# K3NG_Rotator_Interface_V2.net
KiCad netlist of a schematic drawn in EAGLE
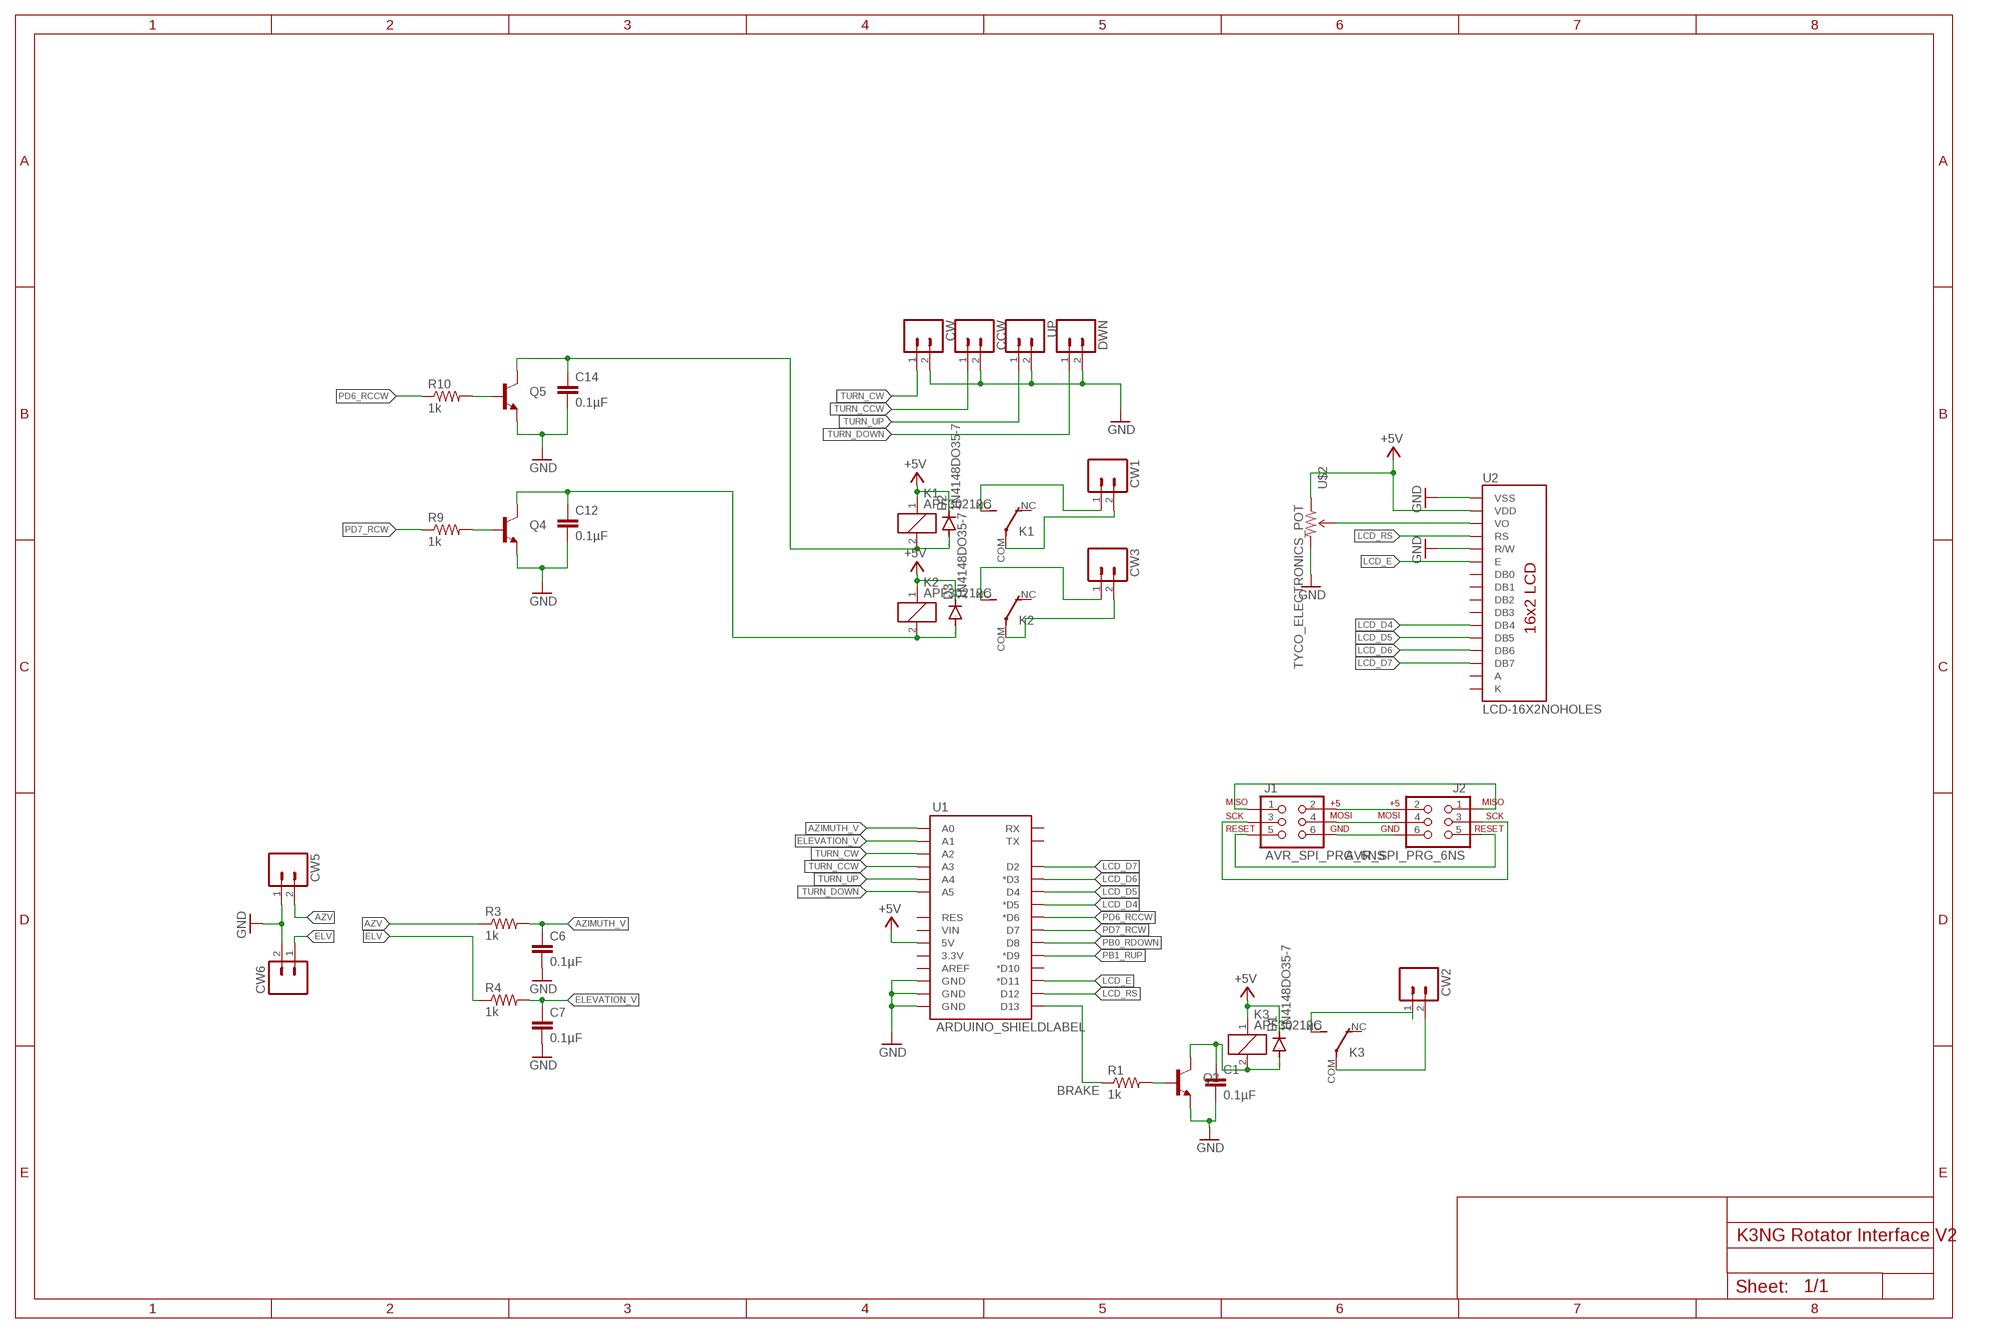
[diagram p0: schematic, sheet 1]

(export (version "E")
  (design (tool "Eeschema 10.0.6"))
  (components
    (comp (ref "C1")
      (value "0.1µF")
      (footprint "eagle-import:0603-CAP")
      (libsource (lib "eagle-import") (part "CAP0603-CAP"))
    )
    (comp (ref "C6")
      (value "0.1µF")
      (footprint "eagle-import:0603-CAP")
      (libsource (lib "eagle-import") (part "CAP0603-CAP"))
    )
    (comp (ref "C7")
      (value "0.1µF")
      (footprint "eagle-import:0603-CAP")
      (libsource (lib "eagle-import") (part "CAP0603-CAP"))
    )
    (comp (ref "C12")
      (value "0.1µF")
      (footprint "eagle-import:0603-CAP")
      (libsource (lib "eagle-import") (part "CAP0603-CAP"))
    )
    (comp (ref "C14")
      (value "0.1µF")
      (footprint "eagle-import:0603-CAP")
      (libsource (lib "eagle-import") (part "CAP0603-CAP"))
    )
    (comp (ref "CCW")
      (value "M02PTH")
      (footprint "eagle-import:1X02")
      (libsource (lib "eagle-import") (part "M02PTH"))
    )
    (comp (ref "CW")
      (value "M02PTH")
      (footprint "eagle-import:1X02")
      (libsource (lib "eagle-import") (part "M02PTH"))
    )
    (comp (ref "CW1")
      (value "M02PTH")
      (footprint "eagle-import:1X02")
      (libsource (lib "eagle-import") (part "M02PTH"))
    )
    (comp (ref "CW2")
      (value "M02PTH")
      (footprint "eagle-import:1X02")
      (libsource (lib "eagle-import") (part "M02PTH"))
    )
    (comp (ref "CW3")
      (value "M02PTH")
      (footprint "eagle-import:1X02")
      (libsource (lib "eagle-import") (part "M02PTH"))
    )
    (comp (ref "CW5")
      (value "M02PTH")
      (footprint "eagle-import:1X02")
      (libsource (lib "eagle-import") (part "M02PTH"))
    )
    (comp (ref "CW6")
      (value "M02PTH")
      (footprint "eagle-import:1X02")
      (libsource (lib "eagle-import") (part "M02PTH"))
    )
    (comp (ref "D1")
      (value "1N4148DO35-7")
      (footprint "eagle-import:DO35-7")
      (libsource (lib "eagle-import") (part "1N4148DO35-7"))
    )
    (comp (ref "D2")
      (value "1N4148DO35-7")
      (footprint "eagle-import:DO35-7")
      (libsource (lib "eagle-import") (part "1N4148DO35-7"))
    )
    (comp (ref "D3")
      (value "1N4148DO35-7")
      (footprint "eagle-import:DO35-7")
      (libsource (lib "eagle-import") (part "1N4148DO35-7"))
    )
    (comp (ref "DWN")
      (value "M02PTH")
      (footprint "eagle-import:1X02")
      (libsource (lib "eagle-import") (part "M02PTH"))
    )
    (comp (ref "J1")
      (value "AVR_SPI_PRG_6NS")
      (footprint "eagle-import:2X3-NS")
      (libsource (lib "eagle-import") (part "AVR_SPI_PRG_6NS"))
    )
    (comp (ref "J2")
      (value "AVR_SPI_PRG_6NS")
      (footprint "eagle-import:2X3-NS")
      (libsource (lib "eagle-import") (part "AVR_SPI_PRG_6NS"))
    )
    (comp (ref "K1")
      (value "APF30212C")
      (footprint "eagle-import:APF30212C")
      (libsource (lib "eagle-import") (part "APF30212C"))
    )
    (comp (ref "K2")
      (value "APF30212C")
      (footprint "eagle-import:APF30212C")
      (libsource (lib "eagle-import") (part "APF30212C"))
    )
    (comp (ref "K3")
      (value "APF30212C")
      (footprint "eagle-import:APF30212C")
      (libsource (lib "eagle-import") (part "APF30212C"))
    )
    (comp (ref "Q2")
      (value "TRANSISTOR_NPNSOT23")
      (footprint "eagle-import:SOT23")
      (libsource (lib "eagle-import") (part "TRANSISTOR_NPNSOT23"))
    )
    (comp (ref "Q4")
      (value "TRANSISTOR_NPNSOT23")
      (footprint "eagle-import:SOT23")
      (libsource (lib "eagle-import") (part "TRANSISTOR_NPNSOT23"))
    )
    (comp (ref "Q5")
      (value "TRANSISTOR_NPNSOT23")
      (footprint "eagle-import:SOT23")
      (libsource (lib "eagle-import") (part "TRANSISTOR_NPNSOT23"))
    )
    (comp (ref "R1")
      (value "1k")
      (footprint "eagle-import:0805")
      (libsource (lib "eagle-import") (part "RESISTOR0805-RES"))
    )
    (comp (ref "R3")
      (value "1k")
      (footprint "eagle-import:0805")
      (libsource (lib "eagle-import") (part "RESISTOR0805-RES"))
    )
    (comp (ref "R4")
      (value "1k")
      (footprint "eagle-import:0805")
      (libsource (lib "eagle-import") (part "RESISTOR0805-RES"))
    )
    (comp (ref "R9")
      (value "1k")
      (footprint "eagle-import:0805")
      (libsource (lib "eagle-import") (part "RESISTOR0805-RES"))
    )
    (comp (ref "R10")
      (value "1k")
      (footprint "eagle-import:0805")
      (libsource (lib "eagle-import") (part "RESISTOR0805-RES"))
    )
    (comp (ref "U$2")
      (value "TYCO_ELECTRONICS_POT")
      (footprint "eagle-import:TYCO_ELECTRONICS_POT")
      (libsource (lib "eagle-import") (part "TYCO_ELECTRONICS_POT"))
    )
    (comp (ref "U1")
      (value "ARDUINO_SHIELDLABEL")
      (footprint "eagle-import:DUEMILANOVE_SHIELD")
      (libsource (lib "eagle-import") (part "ARDUINO_SHIELDLABEL"))
    )
    (comp (ref "U2")
      (value "LCD-16X2NOHOLES")
      (footprint "eagle-import:LCD-16X2_NOHOLES")
      (libsource (lib "eagle-import") (part "LCD-16X2NOHOLES"))
    )
    (comp (ref "UP")
      (value "M02PTH")
      (footprint "eagle-import:1X02")
      (libsource (lib "eagle-import") (part "M02PTH"))
    )
  )
  (nets
    (net (code "1") (name "+5V") (class "Default")
      (node (ref "D1") (pin "C") (pinfunction "C_C") (pintype "passive"))
      (node (ref "D2") (pin "C") (pinfunction "C_C") (pintype "passive"))
      (node (ref "D3") (pin "C") (pinfunction "C_C") (pintype "passive"))
      (node (ref "K1") (pin "1") (pinfunction "1_1") (pintype "passive"))
      (node (ref "K2") (pin "1") (pinfunction "1_1") (pintype "passive"))
      (node (ref "K3") (pin "1") (pinfunction "1_1") (pintype "passive"))
      (node (ref "U$2") (pin "P$1") (pinfunction "CCW_P$1") (pintype "passive"))
      (node (ref "U1") (pin "5V") (pinfunction "5V_5V") (pintype "bidirectional"))
      (node (ref "U2") (pin "2") (pinfunction "VDD_2") (pintype "power_in"))
    )
    (net (code "2") (name "/A") (class "Default")
      (node (ref "U2") (pin "15") (pinfunction "A_15") (pintype "power_in"))
    )
    (net (code "3") (name "/BRAKE") (class "Default")
      (node (ref "R1") (pin "1") (pinfunction "1_1") (pintype "passive"))
      (node (ref "U1") (pin "D13") (pinfunction "D13_D13") (pintype "bidirectional"))
    )
    (net (code "4") (name "/K") (class "Default")
      (node (ref "U2") (pin "16") (pinfunction "K_16") (pintype "power_in"))
    )
    (net (code "5") (name "AZIMUTH_V") (class "Default")
      (node (ref "C6") (pin "1") (pinfunction "1_1") (pintype "passive"))
      (node (ref "R3") (pin "2") (pinfunction "2_2") (pintype "passive"))
      (node (ref "U1") (pin "A0") (pinfunction "A0_A0") (pintype "bidirectional"))
    )
    (net (code "6") (name "AZV") (class "Default")
      (node (ref "CW5") (pin "2") (pinfunction "2_2") (pintype "passive"))
      (node (ref "R3") (pin "1") (pinfunction "1_1") (pintype "passive"))
    )
    (net (code "7") (name "ELEVATION_V") (class "Default")
      (node (ref "C7") (pin "1") (pinfunction "1_1") (pintype "passive"))
      (node (ref "R4") (pin "2") (pinfunction "2_2") (pintype "passive"))
      (node (ref "U1") (pin "A1") (pinfunction "A1_A1") (pintype "bidirectional"))
    )
    (net (code "8") (name "ELV") (class "Default")
      (node (ref "CW6") (pin "1") (pinfunction "1_1") (pintype "passive"))
      (node (ref "R4") (pin "1") (pinfunction "1_1") (pintype "passive"))
    )
    (net (code "9") (name "GND") (class "Default")
      (node (ref "C1") (pin "2") (pinfunction "2_2") (pintype "passive"))
      (node (ref "C12") (pin "2") (pinfunction "2_2") (pintype "passive"))
      (node (ref "C14") (pin "2") (pinfunction "2_2") (pintype "passive"))
      (node (ref "C6") (pin "2") (pinfunction "2_2") (pintype "passive"))
      (node (ref "C7") (pin "2") (pinfunction "2_2") (pintype "passive"))
      (node (ref "CCW") (pin "2") (pinfunction "2_2") (pintype "passive"))
      (node (ref "CW") (pin "2") (pinfunction "2_2") (pintype "passive"))
      (node (ref "CW5") (pin "1") (pinfunction "1_1") (pintype "passive"))
      (node (ref "CW6") (pin "2") (pinfunction "2_2") (pintype "passive"))
      (node (ref "DWN") (pin "2") (pinfunction "2_2") (pintype "passive"))
      (node (ref "Q2") (pin "2") (pinfunction "E_2") (pintype "passive"))
      (node (ref "Q4") (pin "2") (pinfunction "E_2") (pintype "passive"))
      (node (ref "Q5") (pin "2") (pinfunction "E_2") (pintype "passive"))
      (node (ref "U$2") (pin "P$3") (pinfunction "CW_P$3") (pintype "passive"))
      (node (ref "U1") (pin "GND@0") (pinfunction "GND_GND@0") (pintype "bidirectional"))
      (node (ref "U1") (pin "GND@1") (pinfunction "GND_GND@1") (pintype "bidirectional"))
      (node (ref "U1") (pin "GND@2") (pinfunction "GND_GND@2") (pintype "bidirectional"))
      (node (ref "U2") (pin "1") (pinfunction "VSS_1") (pintype "power_in"))
      (node (ref "U2") (pin "5") (pinfunction "R/W_5") (pintype "input"))
      (node (ref "UP") (pin "2") (pinfunction "2_2") (pintype "passive"))
    )
    (net (code "10") (name "LCD_D4") (class "Default")
      (node (ref "U1") (pin "D5") (pinfunction "*D5_D5") (pintype "bidirectional"))
      (node (ref "U2") (pin "11") (pinfunction "DB4_11") (pintype "bidirectional"))
    )
    (net (code "11") (name "LCD_D5") (class "Default")
      (node (ref "U1") (pin "D4") (pinfunction "D4_D4") (pintype "bidirectional"))
      (node (ref "U2") (pin "12") (pinfunction "DB5_12") (pintype "bidirectional"))
    )
    (net (code "12") (name "LCD_D6") (class "Default")
      (node (ref "U1") (pin "D3") (pinfunction "*D3_D3") (pintype "bidirectional"))
      (node (ref "U2") (pin "13") (pinfunction "DB6_13") (pintype "bidirectional"))
    )
    (net (code "13") (name "LCD_D7") (class "Default")
      (node (ref "U1") (pin "D2") (pinfunction "D2_D2") (pintype "bidirectional"))
      (node (ref "U2") (pin "14") (pinfunction "DB7_14") (pintype "bidirectional"))
    )
    (net (code "14") (name "LCD_E") (class "Default")
      (node (ref "U1") (pin "D11") (pinfunction "*D11_D11") (pintype "bidirectional"))
      (node (ref "U2") (pin "6") (pinfunction "E_6") (pintype "input"))
    )
    (net (code "15") (name "LCD_RS") (class "Default")
      (node (ref "U1") (pin "D12") (pinfunction "D12_D12") (pintype "bidirectional"))
      (node (ref "U2") (pin "4") (pinfunction "RS_4") (pintype "input"))
    )
    (net (code "16") (name "Net-(J1-Pad1)") (class "Default")
      (node (ref "J1") (pin "1") (pinfunction "1_1") (pintype "passive"))
      (node (ref "J2") (pin "1") (pinfunction "1_1") (pintype "passive"))
    )
    (net (code "17") (name "Net-(J1-Pad2)") (class "Default")
      (node (ref "J1") (pin "2") (pinfunction "2_2") (pintype "passive"))
      (node (ref "J2") (pin "2") (pinfunction "2_2") (pintype "passive"))
    )
    (net (code "18") (name "Net-(J1-Pad3)") (class "Default")
      (node (ref "J1") (pin "3") (pinfunction "3_3") (pintype "passive"))
      (node (ref "J2") (pin "3") (pinfunction "3_3") (pintype "passive"))
    )
    (net (code "19") (name "Net-(J1-Pad4)") (class "Default")
      (node (ref "J1") (pin "4") (pinfunction "4_4") (pintype "passive"))
      (node (ref "J2") (pin "4") (pinfunction "4_4") (pintype "passive"))
    )
    (net (code "20") (name "Net-(J1-Pad5)") (class "Default")
      (node (ref "J1") (pin "5") (pinfunction "5_5") (pintype "passive"))
      (node (ref "J2") (pin "5") (pinfunction "5_5") (pintype "passive"))
    )
    (net (code "21") (name "Net-(J1-Pad6)") (class "Default")
      (node (ref "J1") (pin "6") (pinfunction "6_6") (pintype "passive"))
      (node (ref "J2") (pin "6") (pinfunction "6_6") (pintype "passive"))
    )
    (net (code "22") (name "Net-(K1B-P)") (class "Default")
      (node (ref "CW1") (pin "2") (pinfunction "2_2") (pintype "passive"))
      (node (ref "K1") (pin "COM") (pinfunction "P_COM") (pintype "passive"))
    )
    (net (code "23") (name "Net-(K1B-S)") (class "Default")
      (node (ref "CW1") (pin "1") (pinfunction "1_1") (pintype "passive"))
      (node (ref "K1") (pin "NO") (pinfunction "S_NO") (pintype "passive"))
    )
    (net (code "24") (name "Net-(K2B-P)") (class "Default")
      (node (ref "CW3") (pin "2") (pinfunction "2_2") (pintype "passive"))
      (node (ref "K2") (pin "COM") (pinfunction "P_COM") (pintype "passive"))
    )
    (net (code "25") (name "Net-(K2B-S)") (class "Default")
      (node (ref "CW3") (pin "1") (pinfunction "1_1") (pintype "passive"))
      (node (ref "K2") (pin "NO") (pinfunction "S_NO") (pintype "passive"))
    )
    (net (code "26") (name "Net-(K3B-P)") (class "Default")
      (node (ref "CW2") (pin "2") (pinfunction "2_2") (pintype "passive"))
      (node (ref "K3") (pin "COM") (pinfunction "P_COM") (pintype "passive"))
    )
    (net (code "27") (name "Net-(K3B-S)") (class "Default")
      (node (ref "CW2") (pin "1") (pinfunction "1_1") (pintype "passive"))
      (node (ref "K3") (pin "NO") (pinfunction "S_NO") (pintype "passive"))
    )
    (net (code "28") (name "Net-(Q2-B)") (class "Default")
      (node (ref "Q2") (pin "1") (pinfunction "B_1") (pintype "passive"))
      (node (ref "R1") (pin "2") (pinfunction "2_2") (pintype "passive"))
    )
    (net (code "29") (name "Net-(Q2-C)") (class "Default")
      (node (ref "C1") (pin "1") (pinfunction "1_1") (pintype "passive"))
      (node (ref "D1") (pin "A") (pinfunction "A_A") (pintype "passive"))
      (node (ref "K3") (pin "2") (pinfunction "2_2") (pintype "passive"))
      (node (ref "Q2") (pin "3") (pinfunction "C_3") (pintype "passive"))
    )
    (net (code "30") (name "Net-(Q4-B)") (class "Default")
      (node (ref "Q4") (pin "1") (pinfunction "B_1") (pintype "passive"))
      (node (ref "R9") (pin "2") (pinfunction "2_2") (pintype "passive"))
    )
    (net (code "31") (name "Net-(Q4-C)") (class "Default")
      (node (ref "C12") (pin "1") (pinfunction "1_1") (pintype "passive"))
      (node (ref "D3") (pin "A") (pinfunction "A_A") (pintype "passive"))
      (node (ref "K2") (pin "2") (pinfunction "2_2") (pintype "passive"))
      (node (ref "Q4") (pin "3") (pinfunction "C_3") (pintype "passive"))
    )
    (net (code "32") (name "Net-(Q5-B)") (class "Default")
      (node (ref "Q5") (pin "1") (pinfunction "B_1") (pintype "passive"))
      (node (ref "R10") (pin "2") (pinfunction "2_2") (pintype "passive"))
    )
    (net (code "33") (name "Net-(Q5-C)") (class "Default")
      (node (ref "C14") (pin "1") (pinfunction "1_1") (pintype "passive"))
      (node (ref "D2") (pin "A") (pinfunction "A_A") (pintype "passive"))
      (node (ref "K1") (pin "2") (pinfunction "2_2") (pintype "passive"))
      (node (ref "Q5") (pin "3") (pinfunction "C_3") (pintype "passive"))
    )
    (net (code "34") (name "Net-(U$2-WIPER)") (class "Default")
      (node (ref "U$2") (pin "P$2") (pinfunction "WIPER_P$2") (pintype "passive"))
      (node (ref "U2") (pin "3") (pinfunction "VO_3") (pintype "bidirectional"))
    )
    (net (code "35") (name "PB0_RDOWN") (class "Default")
      (node (ref "U1") (pin "D8") (pinfunction "D8_D8") (pintype "bidirectional"))
    )
    (net (code "36") (name "PB1_RUP") (class "Default")
      (node (ref "U1") (pin "D9") (pinfunction "*D9_D9") (pintype "bidirectional"))
    )
    (net (code "37") (name "PD6_RCCW") (class "Default")
      (node (ref "R10") (pin "1") (pinfunction "1_1") (pintype "passive"))
      (node (ref "U1") (pin "D6") (pinfunction "*D6_D6") (pintype "bidirectional"))
    )
    (net (code "38") (name "PD7_RCW") (class "Default")
      (node (ref "R9") (pin "1") (pinfunction "1_1") (pintype "passive"))
      (node (ref "U1") (pin "D7") (pinfunction "D7_D7") (pintype "bidirectional"))
    )
    (net (code "39") (name "TURN_CCW") (class "Default")
      (node (ref "CCW") (pin "1") (pinfunction "1_1") (pintype "passive"))
      (node (ref "U1") (pin "A3") (pinfunction "A3_A3") (pintype "bidirectional"))
    )
    (net (code "40") (name "TURN_CW") (class "Default")
      (node (ref "CW") (pin "1") (pinfunction "1_1") (pintype "passive"))
      (node (ref "U1") (pin "A2") (pinfunction "A2_A2") (pintype "bidirectional"))
    )
    (net (code "41") (name "TURN_DOWN") (class "Default")
      (node (ref "DWN") (pin "1") (pinfunction "1_1") (pintype "passive"))
      (node (ref "U1") (pin "A5") (pinfunction "A5_A5") (pintype "bidirectional"))
    )
    (net (code "42") (name "TURN_UP") (class "Default")
      (node (ref "U1") (pin "A4") (pinfunction "A4_A4") (pintype "bidirectional"))
      (node (ref "UP") (pin "1") (pinfunction "1_1") (pintype "passive"))
    )
    (net (code "43") (name "unconnected-(K1B-O-PadNC)") (class "Default")
      (node (ref "K1") (pin "NC") (pinfunction "O_NC") (pintype "passive"))
    )
    (net (code "44") (name "unconnected-(K2B-O-PadNC)") (class "Default")
      (node (ref "K2") (pin "NC") (pinfunction "O_NC") (pintype "passive"))
    )
    (net (code "45") (name "unconnected-(K3B-O-PadNC)") (class "Default")
      (node (ref "K3") (pin "NC") (pinfunction "O_NC") (pintype "passive"))
    )
    (net (code "46") (name "unconnected-(U1-*D10-PadD10)") (class "Default")
      (node (ref "U1") (pin "D10") (pinfunction "*D10_D10") (pintype "bidirectional"))
    )
    (net (code "47") (name "unconnected-(U1-Pad3.3V)") (class "Default")
      (node (ref "U1") (pin "3.3V") (pinfunction "3.3V_3.3V") (pintype "bidirectional"))
    )
    (net (code "48") (name "unconnected-(U1-PadAREF)") (class "Default")
      (node (ref "U1") (pin "AREF") (pinfunction "AREF_AREF") (pintype "bidirectional"))
    )
    (net (code "49") (name "unconnected-(U1-PadRES)") (class "Default")
      (node (ref "U1") (pin "RES") (pinfunction "RES_RES") (pintype "bidirectional"))
    )
    (net (code "50") (name "unconnected-(U1-PadRX)") (class "Default")
      (node (ref "U1") (pin "RX") (pinfunction "RX_RX") (pintype "bidirectional"))
    )
    (net (code "51") (name "unconnected-(U1-PadTX)") (class "Default")
      (node (ref "U1") (pin "TX") (pinfunction "TX_TX") (pintype "bidirectional"))
    )
    (net (code "52") (name "unconnected-(U1-PadVIN)") (class "Default")
      (node (ref "U1") (pin "VIN") (pinfunction "VIN_VIN") (pintype "bidirectional"))
    )
    (net (code "53") (name "unconnected-(U2-DB0-Pad7)") (class "Default")
      (node (ref "U2") (pin "7") (pinfunction "DB0_7") (pintype "bidirectional"))
    )
    (net (code "54") (name "unconnected-(U2-DB1-Pad8)") (class "Default")
      (node (ref "U2") (pin "8") (pinfunction "DB1_8") (pintype "bidirectional"))
    )
    (net (code "55") (name "unconnected-(U2-DB2-Pad9)") (class "Default")
      (node (ref "U2") (pin "9") (pinfunction "DB2_9") (pintype "bidirectional"))
    )
    (net (code "56") (name "unconnected-(U2-DB3-Pad10)") (class "Default")
      (node (ref "U2") (pin "10") (pinfunction "DB3_10") (pintype "bidirectional"))
    )
  )
)
